# AnemometerTHT.net
KiCad netlist of a schematic drawn in EAGLE
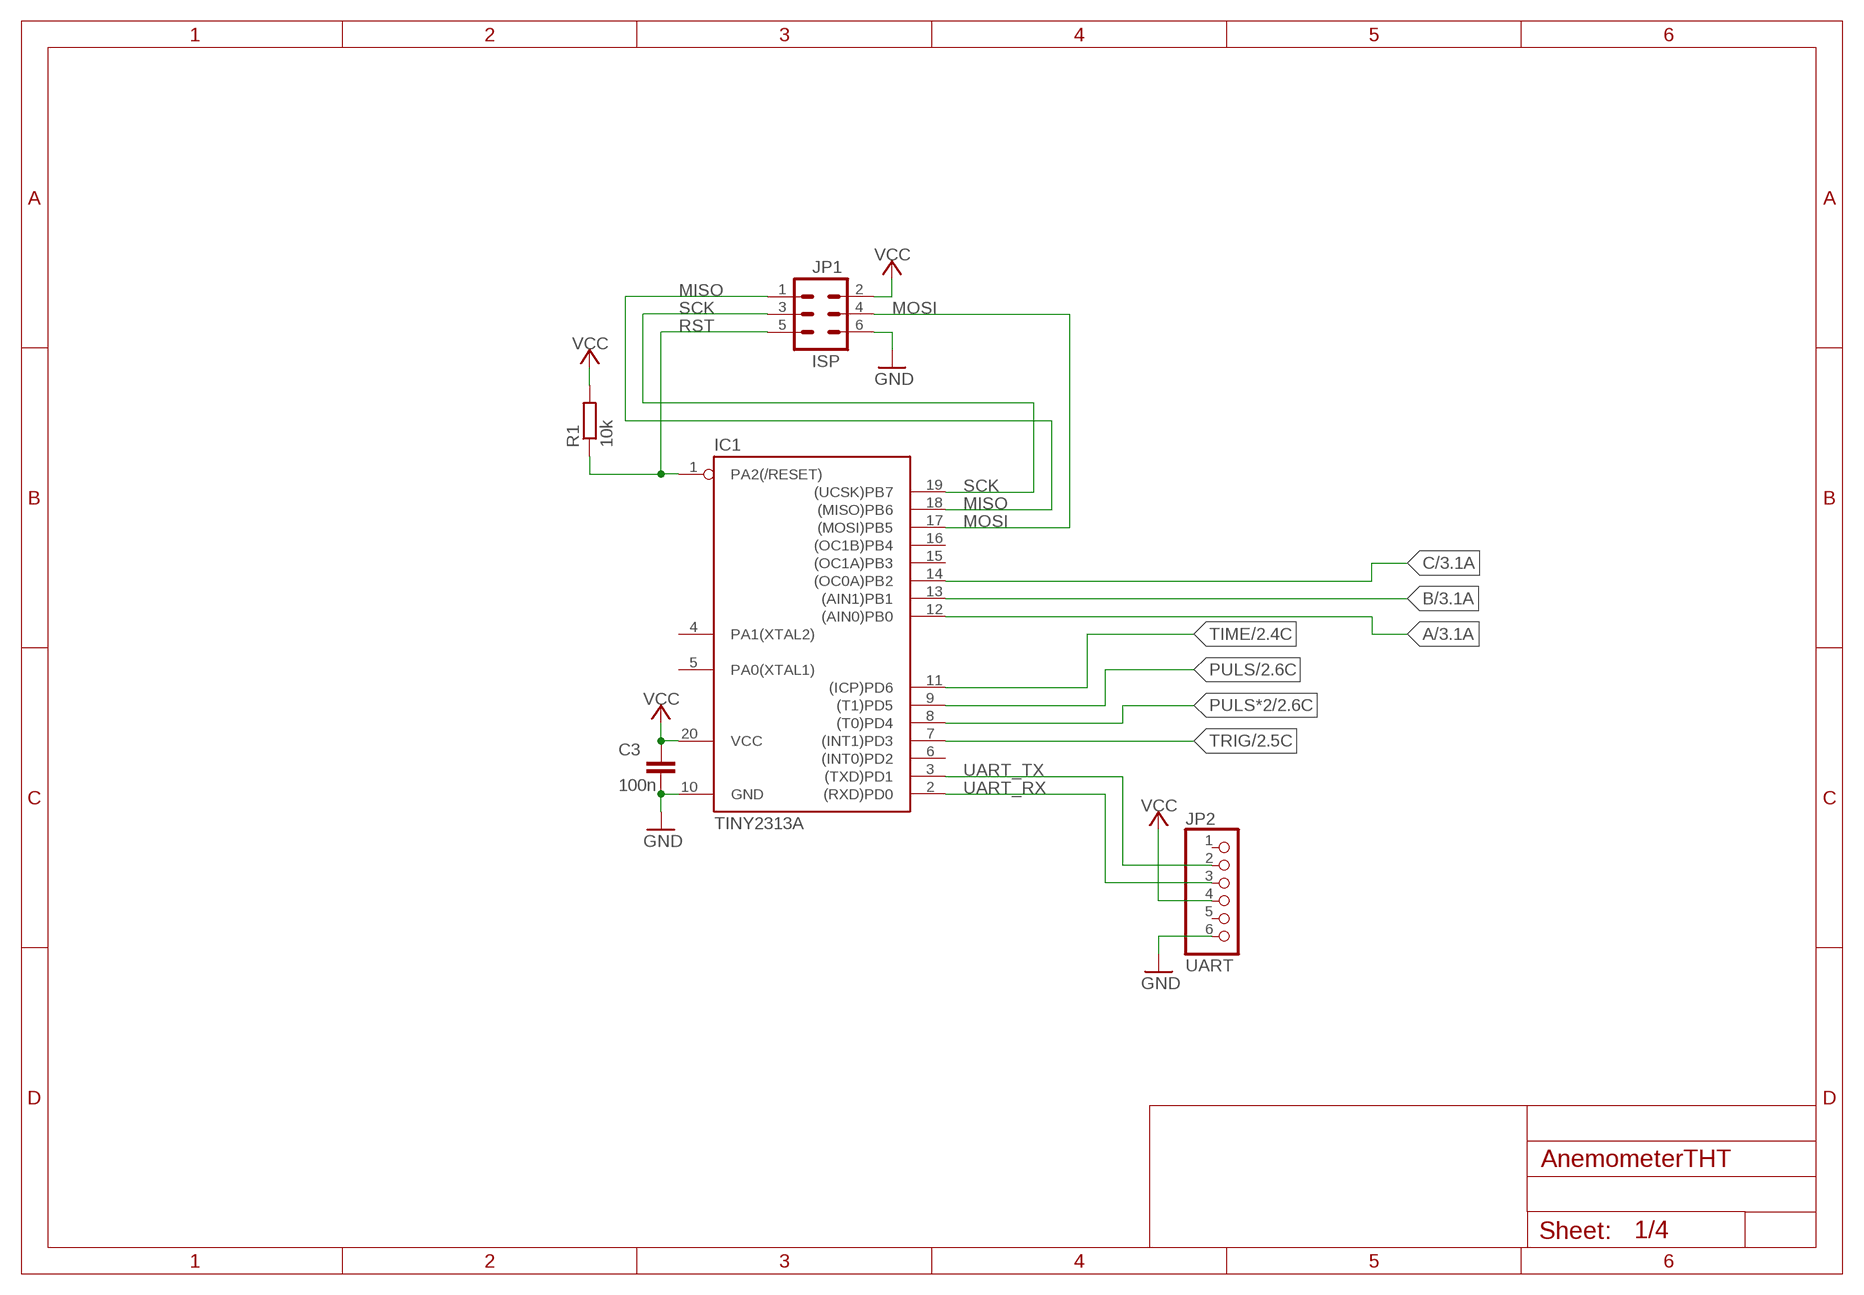
[diagram p0: schematic, sheet 1]
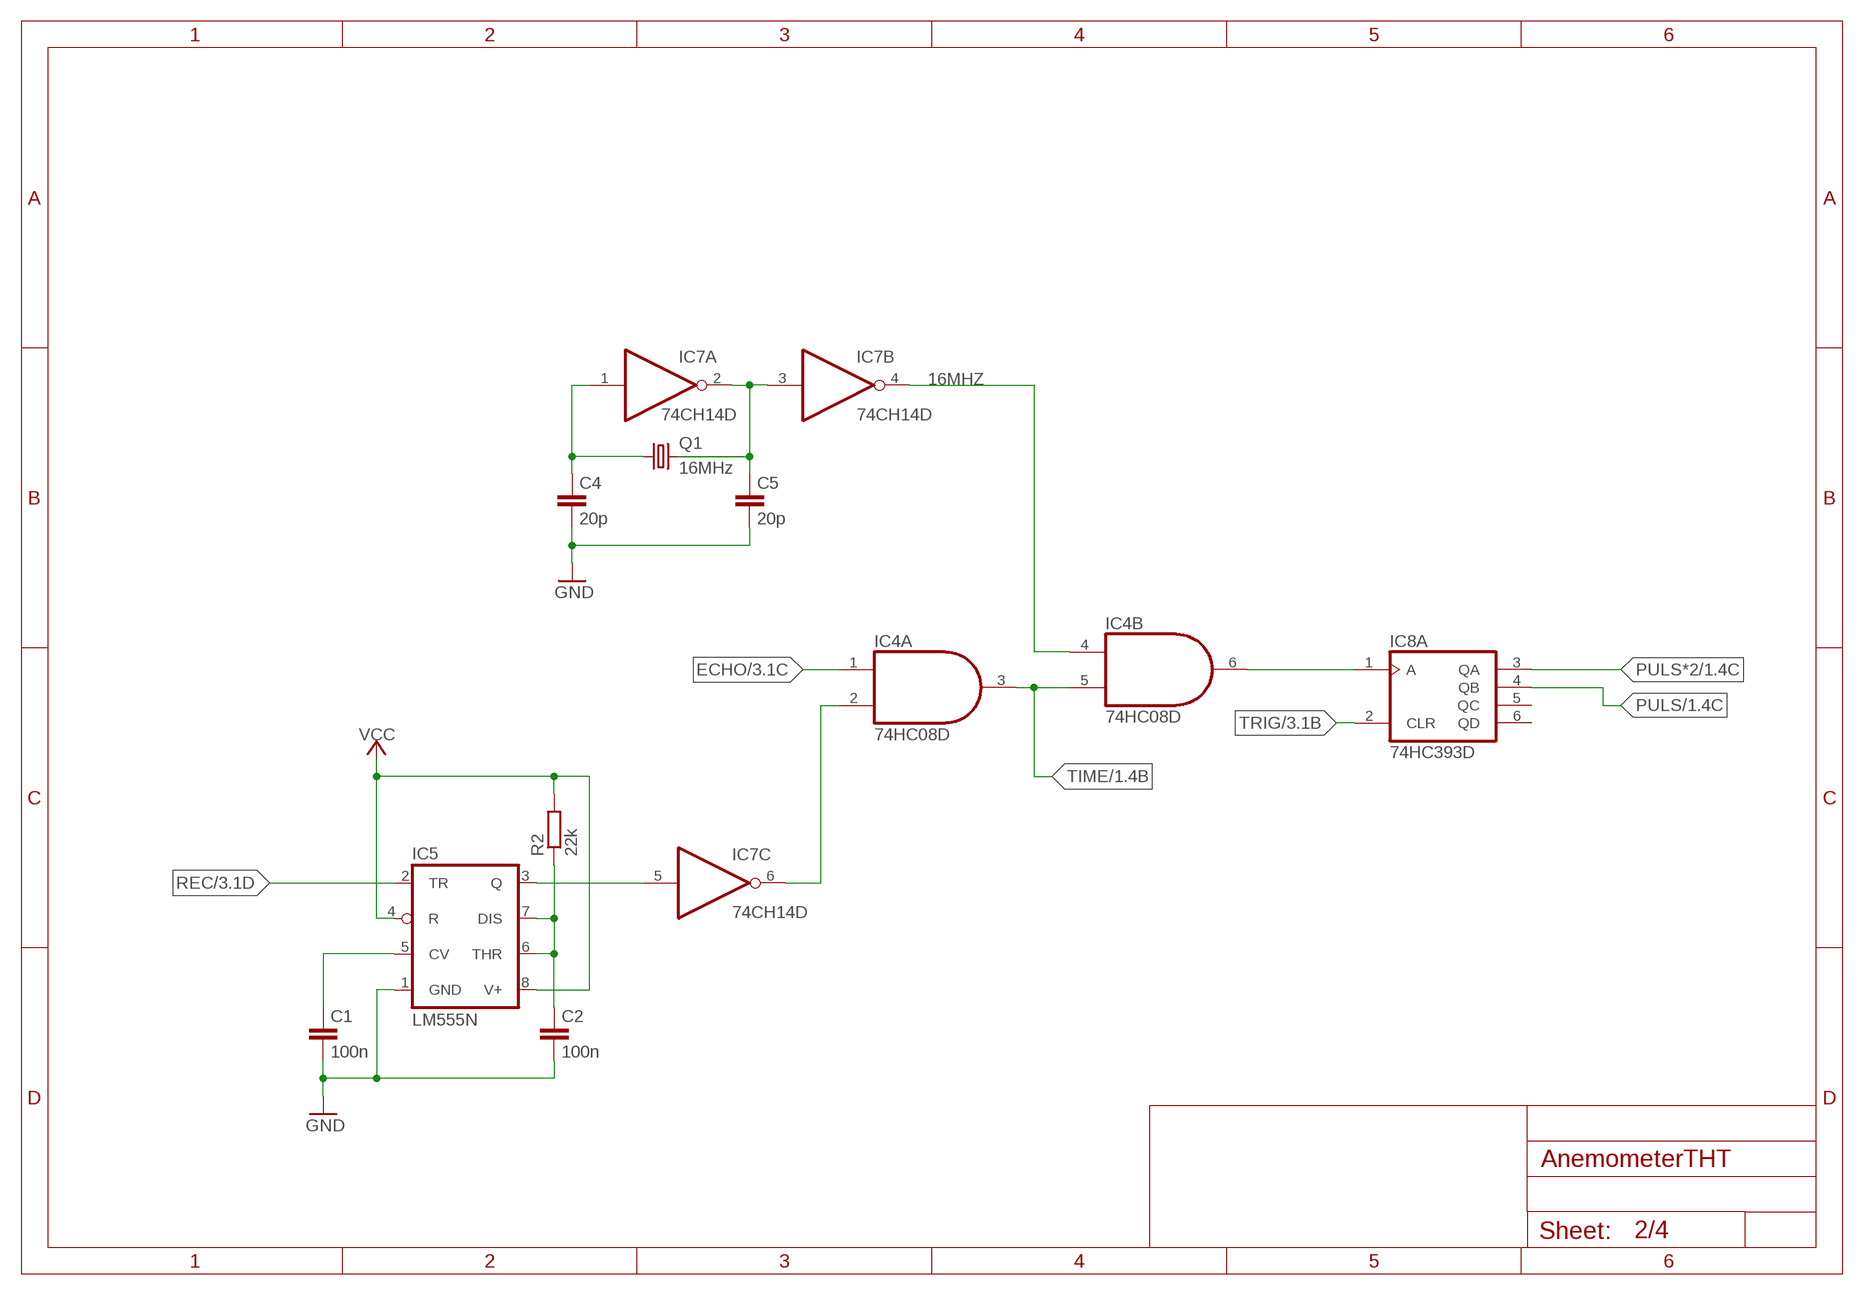
[diagram p1: schematic, sheet 2]
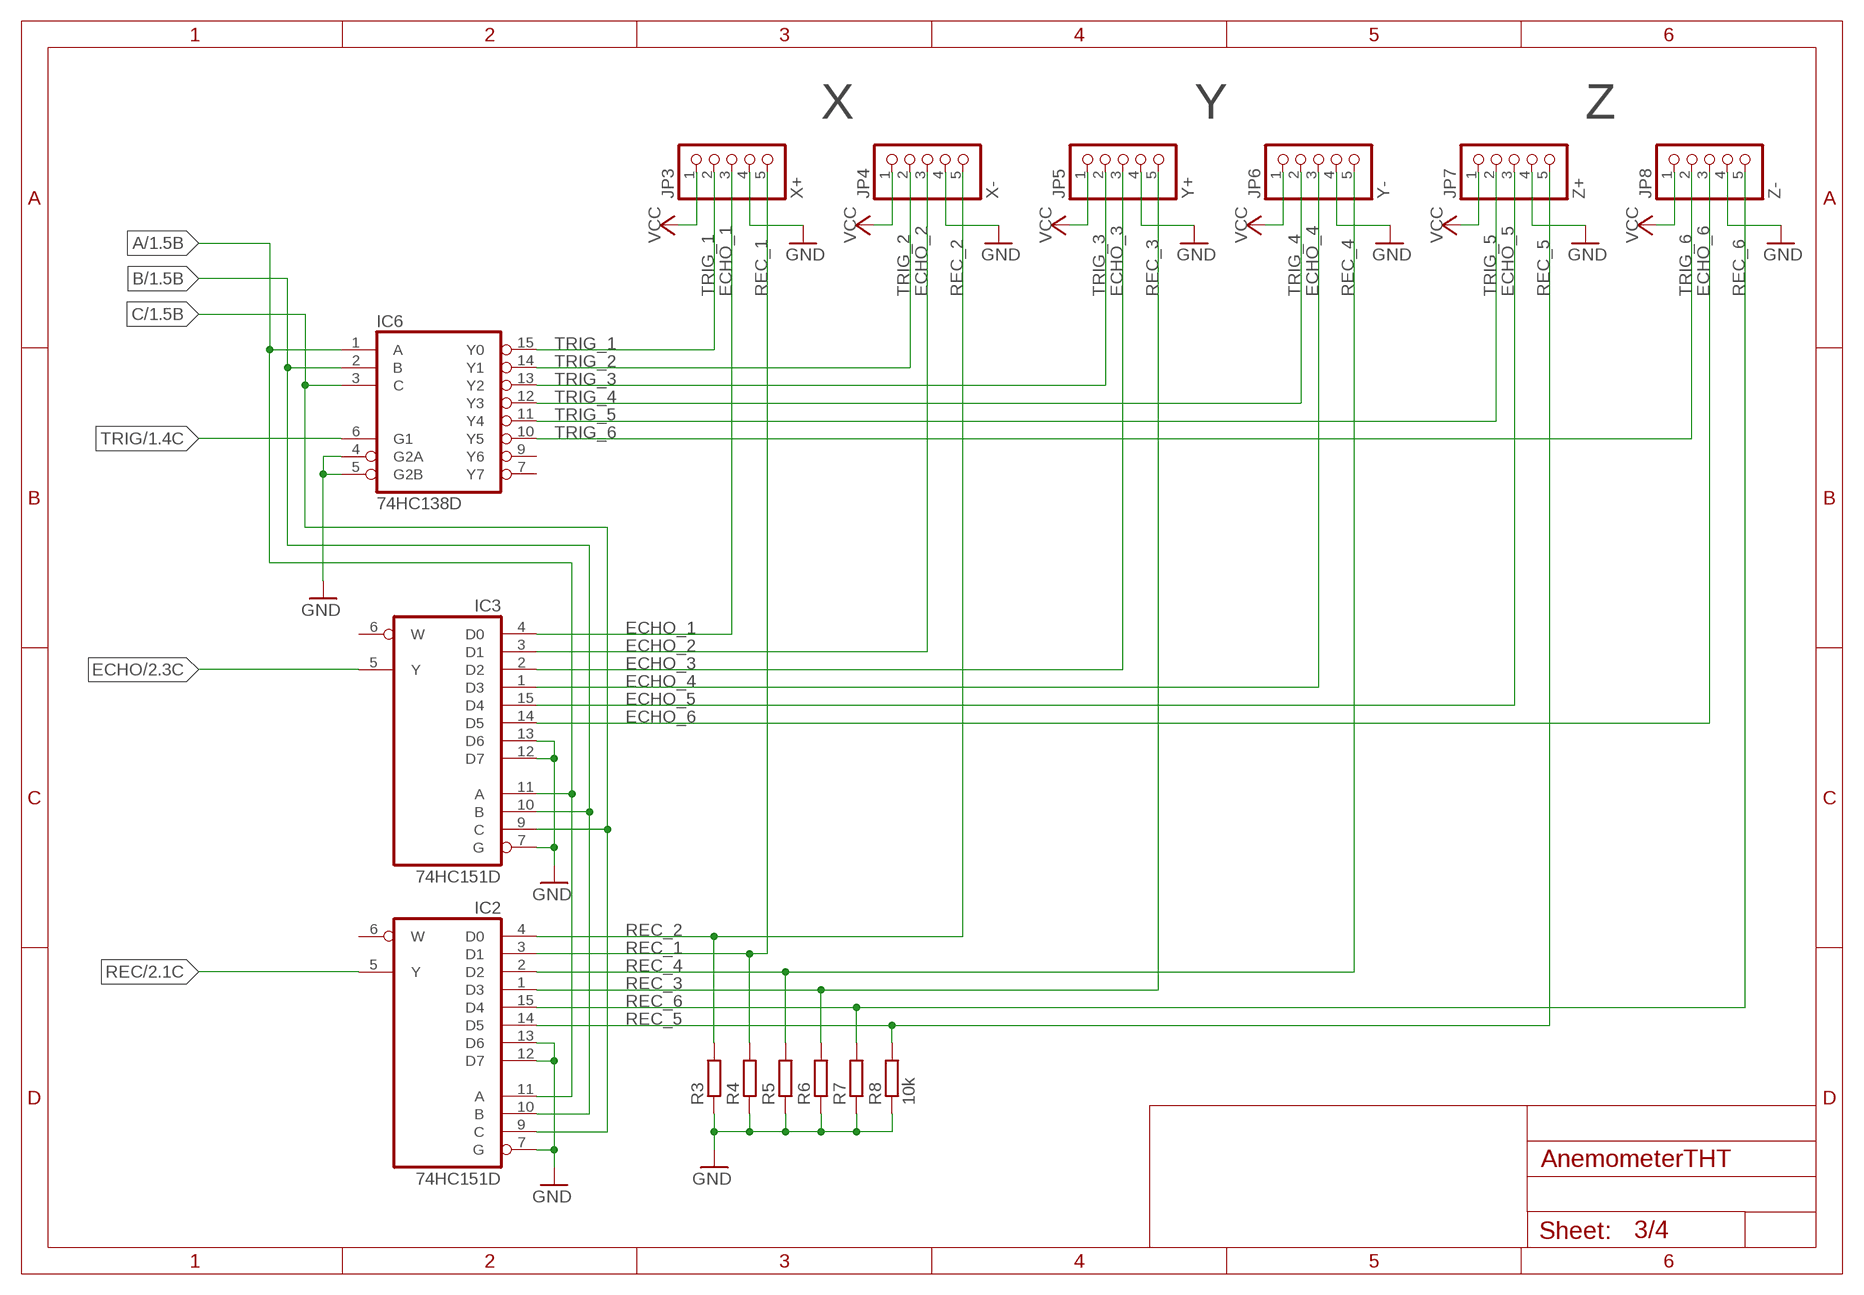
[diagram p2: schematic, sheet 3]
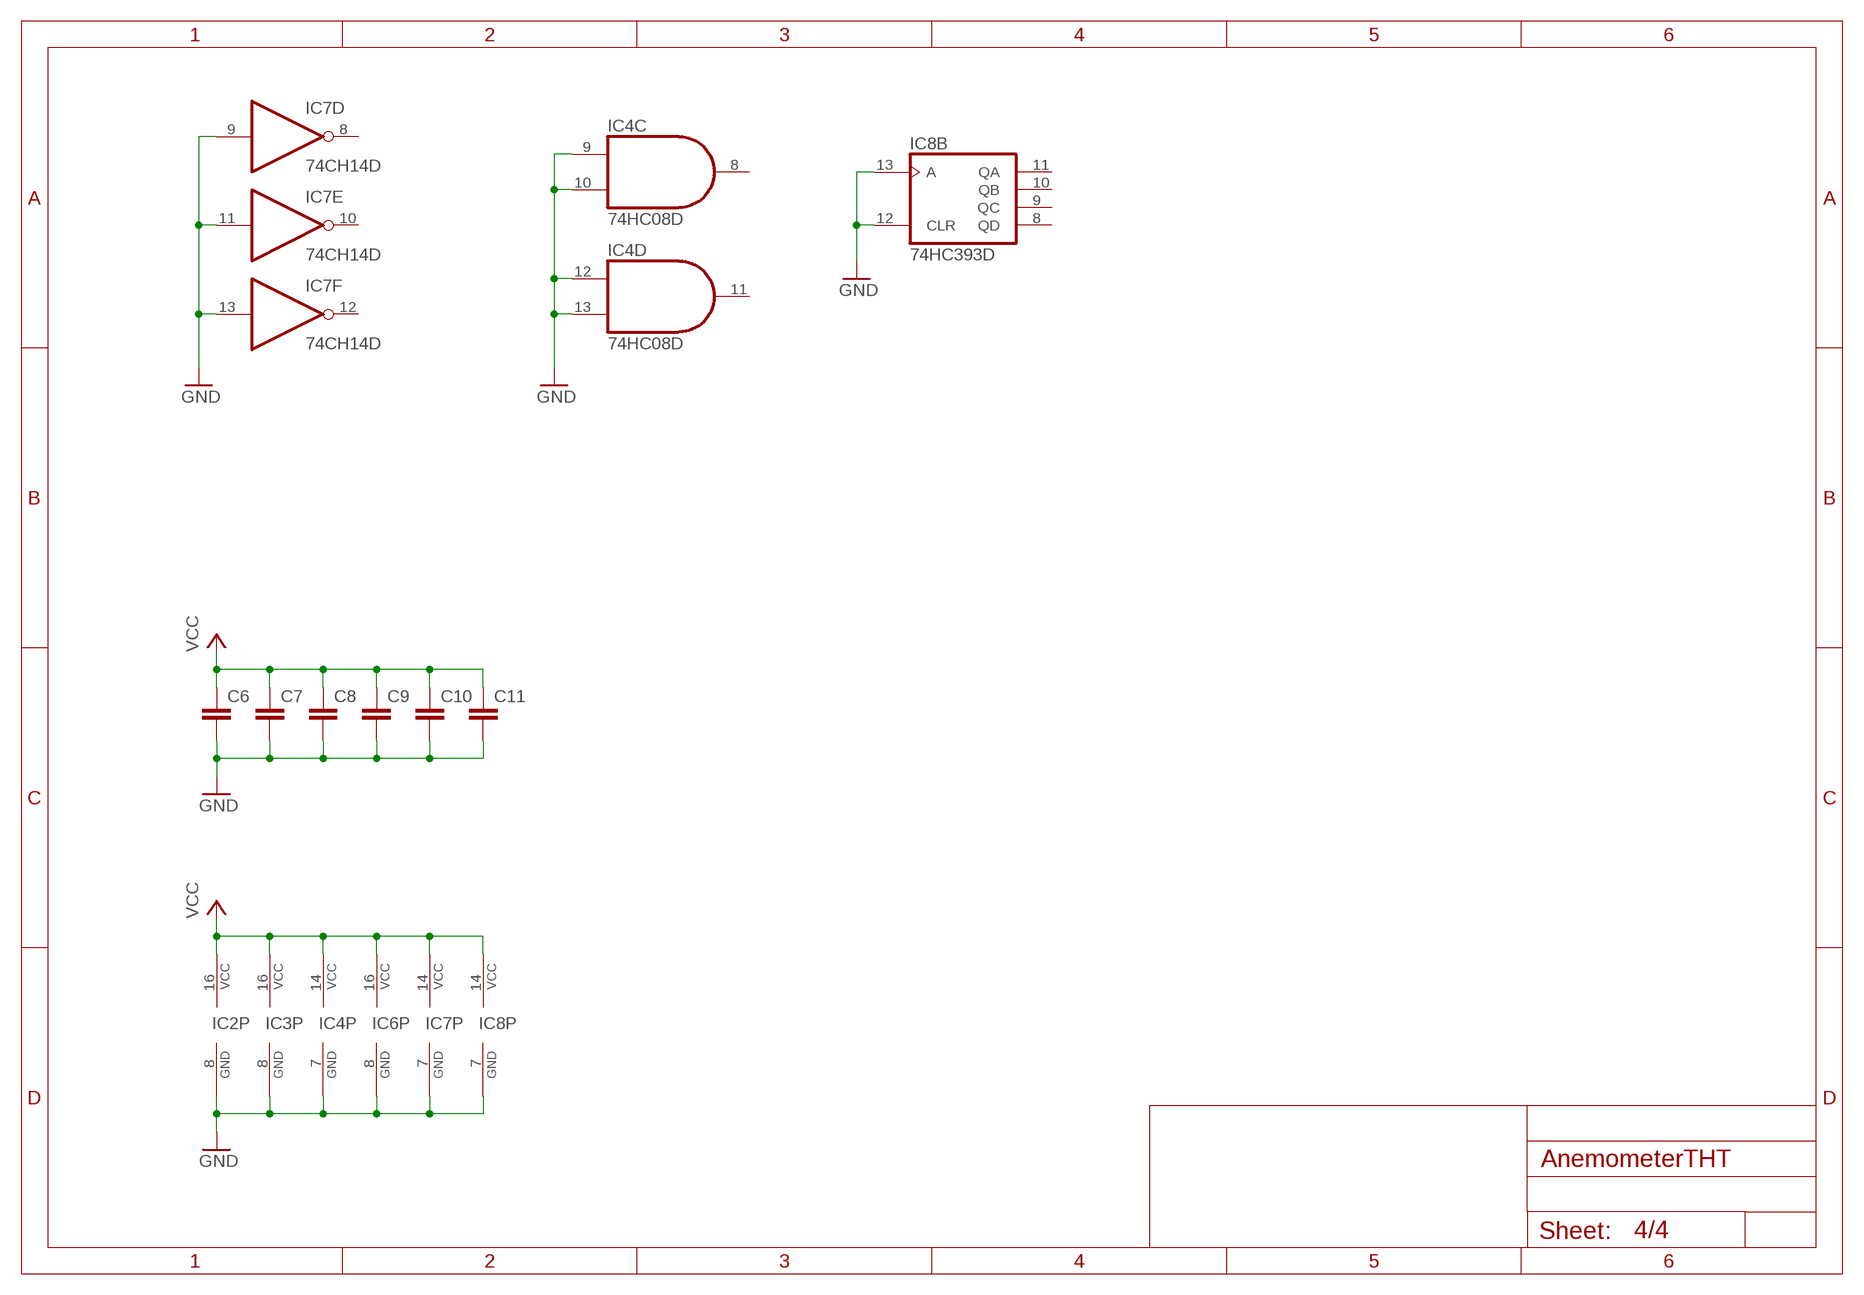
[diagram p3: schematic, sheet 4]

(export (version "E")
  (design (tool "Eeschema 10.0.6"))
  (components
    (comp (ref "IC2")
      (value "74HC151D")
      (footprint "eagle-import:DIL16")
      (libsource (lib "eagle-import") (part "74151NLS"))
    )
    (comp (ref "IC3")
      (value "74HC151D")
      (footprint "eagle-import:DIL16")
      (libsource (lib "eagle-import") (part "74151NLS"))
    )
    (comp (ref "IC6")
      (value "74HC138D")
      (footprint "eagle-import:DIL16")
      (libsource (lib "eagle-import") (part "74138NLS"))
    )
    (comp (ref "JP3")
      (value "X+")
      (footprint "eagle-import:1X05")
      (libsource (lib "eagle-import") (part "PINHD-1X5"))
    )
    (comp (ref "JP4")
      (value "X-")
      (footprint "eagle-import:1X05")
      (libsource (lib "eagle-import") (part "PINHD-1X5"))
    )
    (comp (ref "JP5")
      (value "Y+")
      (footprint "eagle-import:1X05")
      (libsource (lib "eagle-import") (part "PINHD-1X5"))
    )
    (comp (ref "JP6")
      (value "Y-")
      (footprint "eagle-import:1X05")
      (libsource (lib "eagle-import") (part "PINHD-1X5"))
    )
    (comp (ref "JP7")
      (value "Z+")
      (footprint "eagle-import:1X05")
      (libsource (lib "eagle-import") (part "PINHD-1X5"))
    )
    (comp (ref "JP8")
      (value "Z-")
      (footprint "eagle-import:1X05")
      (libsource (lib "eagle-import") (part "PINHD-1X5"))
    )
    (comp (ref "R3")
      (value "10k")
      (footprint "eagle-import:0204_7")
      (libsource (lib "eagle-import") (part "R-EU_0204/7"))
    )
    (comp (ref "R4")
      (value "10k")
      (footprint "eagle-import:0204_7")
      (libsource (lib "eagle-import") (part "R-EU_0204/7"))
    )
    (comp (ref "R5")
      (value "10k")
      (footprint "eagle-import:0204_7")
      (libsource (lib "eagle-import") (part "R-EU_0204/7"))
    )
    (comp (ref "R6")
      (value "10k")
      (footprint "eagle-import:0204_7")
      (libsource (lib "eagle-import") (part "R-EU_0204/7"))
    )
    (comp (ref "R7")
      (value "10k")
      (footprint "eagle-import:0204_7")
      (libsource (lib "eagle-import") (part "R-EU_0204/7"))
    )
    (comp (ref "R8")
      (value "10k")
      (footprint "eagle-import:0204_7")
      (libsource (lib "eagle-import") (part "R-EU_0204/7"))
    )
    (comp (ref "C6")
      (value "C-EU050-030X075")
      (footprint "eagle-import:C050-030X075")
      (libsource (lib "eagle-import") (part "C-EU050-030X075"))
    )
    (comp (ref "C7")
      (value "C-EU050-030X075")
      (footprint "eagle-import:C050-030X075")
      (libsource (lib "eagle-import") (part "C-EU050-030X075"))
    )
    (comp (ref "C8")
      (value "C-EU050-030X075")
      (footprint "eagle-import:C050-030X075")
      (libsource (lib "eagle-import") (part "C-EU050-030X075"))
    )
    (comp (ref "C9")
      (value "C-EU050-030X075")
      (footprint "eagle-import:C050-030X075")
      (libsource (lib "eagle-import") (part "C-EU050-030X075"))
    )
    (comp (ref "C10")
      (value "C-EU050-030X075")
      (footprint "eagle-import:C050-030X075")
      (libsource (lib "eagle-import") (part "C-EU050-030X075"))
    )
    (comp (ref "C11")
      (value "C-EU050-030X075")
      (footprint "eagle-import:C050-030X075")
      (libsource (lib "eagle-import") (part "C-EU050-030X075"))
    )
    (comp (ref "IC4")
      (value "74HC08D")
      (footprint "eagle-import:DIL14")
      (libsource (lib "eagle-import") (part "7408NALS"))
    )
    (comp (ref "IC7")
      (value "74CH14D")
      (footprint "eagle-import:DIL14")
      (libsource (lib "eagle-import") (part "7404NALS"))
    )
    (comp (ref "IC8")
      (value "74HC393D")
      (footprint "eagle-import:DIL14")
      (libsource (lib "eagle-import") (part "74393NLS"))
    )
    (comp (ref "C1")
      (value "100n")
      (footprint "eagle-import:C050-030X075")
      (libsource (lib "eagle-import") (part "C-EU050-030X075"))
    )
    (comp (ref "C2")
      (value "100n")
      (footprint "eagle-import:C050-030X075")
      (libsource (lib "eagle-import") (part "C-EU050-030X075"))
    )
    (comp (ref "C4")
      (value "20p")
      (footprint "eagle-import:C050-030X075")
      (libsource (lib "eagle-import") (part "C-EU050-030X075"))
    )
    (comp (ref "C5")
      (value "20p")
      (footprint "eagle-import:C050-030X075")
      (libsource (lib "eagle-import") (part "C-EU050-030X075"))
    )
    (comp (ref "IC5")
      (value "LM555N")
      (footprint "eagle-import:DIL08")
      (libsource (lib "eagle-import") (part "555NLM"))
    )
    (comp (ref "Q1")
      (value "16MHz")
      (footprint "eagle-import:HC49U70")
      (libsource (lib "eagle-import") (part "CRYSTALHC49U70"))
    )
    (comp (ref "R2")
      (value "22k")
      (footprint "eagle-import:0204_7")
      (libsource (lib "eagle-import") (part "R-EU_0204/7"))
    )
    (comp (ref "C3")
      (value "100n")
      (footprint "eagle-import:C050-030X075")
      (libsource (lib "eagle-import") (part "C-EU050-030X075"))
    )
    (comp (ref "IC1")
      (value "TINY2313A")
      (footprint "eagle-import:DIL20")
      (libsource (lib "eagle-import") (part "TINY2313-P"))
    )
    (comp (ref "JP1")
      (value "ISP")
      (footprint "eagle-import:ML6")
      (libsource (lib "eagle-import") (part "ML6"))
    )
    (comp (ref "JP2")
      (value "UART")
      (footprint "eagle-import:1X06")
      (libsource (lib "eagle-import") (part "PINHD-1X6"))
    )
    (comp (ref "R1")
      (value "10k")
      (footprint "eagle-import:0204_7")
      (libsource (lib "eagle-import") (part "R-EU_0204/7"))
    )
  )
  (nets
    (net (code "1") (name "16MHZ") (class "Default")
      (node (ref "IC4") (pin "4") (pinfunction "I0_4") (pintype "input"))
      (node (ref "IC7") (pin "4") (pinfunction "O_4") (pintype "output"))
    )
    (net (code "2") (name "A") (class "Default")
      (node (ref "IC1") (pin "12") (pinfunction "(AIN0)PB0_12") (pintype "bidirectional"))
      (node (ref "IC2") (pin "11") (pinfunction "A_11") (pintype "input"))
      (node (ref "IC3") (pin "11") (pinfunction "A_11") (pintype "input"))
      (node (ref "IC6") (pin "1") (pinfunction "A_1") (pintype "input"))
    )
    (net (code "3") (name "B") (class "Default")
      (node (ref "IC1") (pin "13") (pinfunction "(AIN1)PB1_13") (pintype "bidirectional"))
      (node (ref "IC2") (pin "10") (pinfunction "B_10") (pintype "input"))
      (node (ref "IC3") (pin "10") (pinfunction "B_10") (pintype "input"))
      (node (ref "IC6") (pin "2") (pinfunction "B_2") (pintype "input"))
    )
    (net (code "4") (name "C") (class "Default")
      (node (ref "IC1") (pin "14") (pinfunction "(OC0A)PB2_14") (pintype "bidirectional"))
      (node (ref "IC2") (pin "9") (pinfunction "C_9") (pintype "input"))
      (node (ref "IC3") (pin "9") (pinfunction "C_9") (pintype "input"))
      (node (ref "IC6") (pin "3") (pinfunction "C_3") (pintype "input"))
    )
    (net (code "5") (name "ECHO") (class "Default")
      (node (ref "IC3") (pin "5") (pinfunction "Y_5") (pintype "output"))
      (node (ref "IC4") (pin "1") (pinfunction "I0_1") (pintype "input"))
    )
    (net (code "6") (name "ECHO_1") (class "Default")
      (node (ref "IC3") (pin "4") (pinfunction "D0_4") (pintype "input"))
      (node (ref "JP3") (pin "3") (pinfunction "3_3") (pintype "passive"))
    )
    (net (code "7") (name "ECHO_2") (class "Default")
      (node (ref "IC3") (pin "3") (pinfunction "D1_3") (pintype "input"))
      (node (ref "JP4") (pin "3") (pinfunction "3_3") (pintype "passive"))
    )
    (net (code "8") (name "ECHO_3") (class "Default")
      (node (ref "IC3") (pin "2") (pinfunction "D2_2") (pintype "input"))
      (node (ref "JP5") (pin "3") (pinfunction "3_3") (pintype "passive"))
    )
    (net (code "9") (name "ECHO_4") (class "Default")
      (node (ref "IC3") (pin "1") (pinfunction "D3_1") (pintype "input"))
      (node (ref "JP6") (pin "3") (pinfunction "3_3") (pintype "passive"))
    )
    (net (code "10") (name "ECHO_5") (class "Default")
      (node (ref "IC3") (pin "15") (pinfunction "D4_15") (pintype "input"))
      (node (ref "JP7") (pin "3") (pinfunction "3_3") (pintype "passive"))
    )
    (net (code "11") (name "ECHO_6") (class "Default")
      (node (ref "IC3") (pin "14") (pinfunction "D5_14") (pintype "input"))
      (node (ref "JP8") (pin "3") (pinfunction "3_3") (pintype "passive"))
    )
    (net (code "12") (name "GND") (class "Default")
      (node (ref "C1") (pin "2") (pinfunction "2_2") (pintype "passive"))
      (node (ref "C10") (pin "2") (pinfunction "2_2") (pintype "passive"))
      (node (ref "C11") (pin "2") (pinfunction "2_2") (pintype "passive"))
      (node (ref "C2") (pin "2") (pinfunction "2_2") (pintype "passive"))
      (node (ref "C3") (pin "2") (pinfunction "2_2") (pintype "passive"))
      (node (ref "C4") (pin "2") (pinfunction "2_2") (pintype "passive"))
      (node (ref "C5") (pin "2") (pinfunction "2_2") (pintype "passive"))
      (node (ref "C6") (pin "2") (pinfunction "2_2") (pintype "passive"))
      (node (ref "C7") (pin "2") (pinfunction "2_2") (pintype "passive"))
      (node (ref "C8") (pin "2") (pinfunction "2_2") (pintype "passive"))
      (node (ref "C9") (pin "2") (pinfunction "2_2") (pintype "passive"))
      (node (ref "IC1") (pin "10") (pinfunction "GND_10") (pintype "power_in"))
      (node (ref "IC2") (pin "12") (pinfunction "D7_12") (pintype "input"))
      (node (ref "IC2") (pin "13") (pinfunction "D6_13") (pintype "input"))
      (node (ref "IC2") (pin "7") (pinfunction "G_7") (pintype "input"))
      (node (ref "IC2") (pin "8") (pinfunction "GND_8") (pintype "power_in"))
      (node (ref "IC3") (pin "12") (pinfunction "D7_12") (pintype "input"))
      (node (ref "IC3") (pin "13") (pinfunction "D6_13") (pintype "input"))
      (node (ref "IC3") (pin "7") (pinfunction "G_7") (pintype "input"))
      (node (ref "IC3") (pin "8") (pinfunction "GND_8") (pintype "power_in"))
      (node (ref "IC4") (pin "10") (pinfunction "I1_10") (pintype "input"))
      (node (ref "IC4") (pin "12") (pinfunction "I0_12") (pintype "input"))
      (node (ref "IC4") (pin "13") (pinfunction "I1_13") (pintype "input"))
      (node (ref "IC4") (pin "7") (pinfunction "GND_7") (pintype "power_in"))
      (node (ref "IC4") (pin "9") (pinfunction "I0_9") (pintype "input"))
      (node (ref "IC5") (pin "1") (pinfunction "GND_1") (pintype "power_in"))
      (node (ref "IC6") (pin "4") (pinfunction "G2A_4") (pintype "input"))
      (node (ref "IC6") (pin "5") (pinfunction "G2B_5") (pintype "input"))
      (node (ref "IC6") (pin "8") (pinfunction "GND_8") (pintype "power_in"))
      (node (ref "IC7") (pin "11") (pinfunction "I_11") (pintype "input"))
      (node (ref "IC7") (pin "13") (pinfunction "I_13") (pintype "input"))
      (node (ref "IC7") (pin "7") (pinfunction "GND_7") (pintype "power_in"))
      (node (ref "IC7") (pin "9") (pinfunction "I_9") (pintype "input"))
      (node (ref "IC8") (pin "12") (pinfunction "CLR_12") (pintype "input"))
      (node (ref "IC8") (pin "13") (pinfunction "A_13") (pintype "input"))
      (node (ref "IC8") (pin "7") (pinfunction "GND_7") (pintype "power_in"))
      (node (ref "JP1") (pin "6") (pinfunction "6_6") (pintype "passive"))
      (node (ref "JP2") (pin "6") (pinfunction "6_6") (pintype "passive"))
      (node (ref "JP3") (pin "4") (pinfunction "4_4") (pintype "passive"))
      (node (ref "JP4") (pin "4") (pinfunction "4_4") (pintype "passive"))
      (node (ref "JP5") (pin "4") (pinfunction "4_4") (pintype "passive"))
      (node (ref "JP6") (pin "4") (pinfunction "4_4") (pintype "passive"))
      (node (ref "JP7") (pin "4") (pinfunction "4_4") (pintype "passive"))
      (node (ref "JP8") (pin "4") (pinfunction "4_4") (pintype "passive"))
      (node (ref "R3") (pin "1") (pinfunction "1_1") (pintype "passive"))
      (node (ref "R4") (pin "1") (pinfunction "1_1") (pintype "passive"))
      (node (ref "R5") (pin "1") (pinfunction "1_1") (pintype "passive"))
      (node (ref "R6") (pin "1") (pinfunction "1_1") (pintype "passive"))
      (node (ref "R7") (pin "1") (pinfunction "1_1") (pintype "passive"))
      (node (ref "R8") (pin "1") (pinfunction "1_1") (pintype "passive"))
    )
    (net (code "13") (name "MISO") (class "Default")
      (node (ref "IC1") (pin "18") (pinfunction "(MISO)PB6_18") (pintype "bidirectional"))
      (node (ref "JP1") (pin "1") (pinfunction "1_1") (pintype "passive"))
    )
    (net (code "14") (name "MOSI") (class "Default")
      (node (ref "IC1") (pin "17") (pinfunction "(MOSI)PB5_17") (pintype "bidirectional"))
      (node (ref "JP1") (pin "4") (pinfunction "4_4") (pintype "passive"))
    )
    (net (code "15") (name "Net-(IC4A-I1)") (class "Default")
      (node (ref "IC4") (pin "2") (pinfunction "I1_2") (pintype "input"))
      (node (ref "IC7") (pin "6") (pinfunction "O_6") (pintype "output"))
    )
    (net (code "16") (name "Net-(IC4B-O)") (class "Default")
      (node (ref "IC4") (pin "6") (pinfunction "O_6") (pintype "output"))
      (node (ref "IC8") (pin "1") (pinfunction "A_1") (pintype "input"))
    )
    (net (code "17") (name "Net-(IC5-CV)") (class "Default")
      (node (ref "C1") (pin "1") (pinfunction "1_1") (pintype "passive"))
      (node (ref "IC5") (pin "5") (pinfunction "CV_5") (pintype "input"))
    )
    (net (code "18") (name "Net-(IC5-DIS)") (class "Default")
      (node (ref "C2") (pin "1") (pinfunction "1_1") (pintype "passive"))
      (node (ref "IC5") (pin "6") (pinfunction "THR_6") (pintype "input"))
      (node (ref "IC5") (pin "7") (pinfunction "DIS_7") (pintype "input"))
      (node (ref "R2") (pin "1") (pinfunction "1_1") (pintype "passive"))
    )
    (net (code "19") (name "Net-(IC5-Q)") (class "Default")
      (node (ref "IC5") (pin "3") (pinfunction "Q_3") (pintype "output"))
      (node (ref "IC7") (pin "5") (pinfunction "I_5") (pintype "input"))
    )
    (net (code "20") (name "Net-(IC7A-I)") (class "Default")
      (node (ref "C4") (pin "1") (pinfunction "1_1") (pintype "passive"))
      (node (ref "IC7") (pin "1") (pinfunction "I_1") (pintype "input"))
      (node (ref "Q1") (pin "1") (pinfunction "1_1") (pintype "passive"))
    )
    (net (code "21") (name "Net-(IC7A-O)") (class "Default")
      (node (ref "C5") (pin "1") (pinfunction "1_1") (pintype "passive"))
      (node (ref "IC7") (pin "2") (pinfunction "O_2") (pintype "output"))
      (node (ref "IC7") (pin "3") (pinfunction "I_3") (pintype "input"))
      (node (ref "Q1") (pin "2") (pinfunction "2_2") (pintype "passive"))
    )
    (net (code "22") (name "PULS") (class "Default")
      (node (ref "IC1") (pin "9") (pinfunction "(T1)PD5_9") (pintype "bidirectional"))
      (node (ref "IC8") (pin "4") (pinfunction "QB_4") (pintype "output"))
    )
    (net (code "23") (name "PULS*2") (class "Default")
      (node (ref "IC1") (pin "8") (pinfunction "(T0)PD4_8") (pintype "bidirectional"))
      (node (ref "IC8") (pin "3") (pinfunction "QA_3") (pintype "output"))
    )
    (net (code "24") (name "REC") (class "Default")
      (node (ref "IC2") (pin "5") (pinfunction "Y_5") (pintype "output"))
      (node (ref "IC5") (pin "2") (pinfunction "TR_2") (pintype "input"))
    )
    (net (code "25") (name "REC_1") (class "Default")
      (node (ref "IC2") (pin "3") (pinfunction "D1_3") (pintype "input"))
      (node (ref "JP3") (pin "5") (pinfunction "5_5") (pintype "passive"))
      (node (ref "R4") (pin "2") (pinfunction "2_2") (pintype "passive"))
    )
    (net (code "26") (name "REC_2") (class "Default")
      (node (ref "IC2") (pin "4") (pinfunction "D0_4") (pintype "input"))
      (node (ref "JP4") (pin "5") (pinfunction "5_5") (pintype "passive"))
      (node (ref "R3") (pin "2") (pinfunction "2_2") (pintype "passive"))
    )
    (net (code "27") (name "REC_3") (class "Default")
      (node (ref "IC2") (pin "1") (pinfunction "D3_1") (pintype "input"))
      (node (ref "JP5") (pin "5") (pinfunction "5_5") (pintype "passive"))
      (node (ref "R6") (pin "2") (pinfunction "2_2") (pintype "passive"))
    )
    (net (code "28") (name "REC_4") (class "Default")
      (node (ref "IC2") (pin "2") (pinfunction "D2_2") (pintype "input"))
      (node (ref "JP6") (pin "5") (pinfunction "5_5") (pintype "passive"))
      (node (ref "R5") (pin "2") (pinfunction "2_2") (pintype "passive"))
    )
    (net (code "29") (name "REC_5") (class "Default")
      (node (ref "IC2") (pin "14") (pinfunction "D5_14") (pintype "input"))
      (node (ref "JP7") (pin "5") (pinfunction "5_5") (pintype "passive"))
      (node (ref "R8") (pin "2") (pinfunction "2_2") (pintype "passive"))
    )
    (net (code "30") (name "REC_6") (class "Default")
      (node (ref "IC2") (pin "15") (pinfunction "D4_15") (pintype "input"))
      (node (ref "JP8") (pin "5") (pinfunction "5_5") (pintype "passive"))
      (node (ref "R7") (pin "2") (pinfunction "2_2") (pintype "passive"))
    )
    (net (code "31") (name "RST") (class "Default")
      (node (ref "IC1") (pin "1") (pinfunction "PA2(/RESET)_1") (pintype "input"))
      (node (ref "JP1") (pin "5") (pinfunction "5_5") (pintype "passive"))
      (node (ref "R1") (pin "1") (pinfunction "1_1") (pintype "passive"))
    )
    (net (code "32") (name "SCK") (class "Default")
      (node (ref "IC1") (pin "19") (pinfunction "(UCSK)PB7_19") (pintype "bidirectional"))
      (node (ref "JP1") (pin "3") (pinfunction "3_3") (pintype "passive"))
    )
    (net (code "33") (name "TIME") (class "Default")
      (node (ref "IC1") (pin "11") (pinfunction "(ICP)PD6_11") (pintype "bidirectional"))
      (node (ref "IC4") (pin "3") (pinfunction "O_3") (pintype "output"))
      (node (ref "IC4") (pin "5") (pinfunction "I1_5") (pintype "input"))
    )
    (net (code "34") (name "TRIG") (class "Default")
      (node (ref "IC1") (pin "7") (pinfunction "(INT1)PD3_7") (pintype "bidirectional"))
      (node (ref "IC6") (pin "6") (pinfunction "G1_6") (pintype "input"))
      (node (ref "IC8") (pin "2") (pinfunction "CLR_2") (pintype "input"))
    )
    (net (code "35") (name "TRIG_1") (class "Default")
      (node (ref "IC6") (pin "15") (pinfunction "Y0_15") (pintype "output"))
      (node (ref "JP3") (pin "2") (pinfunction "2_2") (pintype "passive"))
    )
    (net (code "36") (name "TRIG_2") (class "Default")
      (node (ref "IC6") (pin "14") (pinfunction "Y1_14") (pintype "output"))
      (node (ref "JP4") (pin "2") (pinfunction "2_2") (pintype "passive"))
    )
    (net (code "37") (name "TRIG_3") (class "Default")
      (node (ref "IC6") (pin "13") (pinfunction "Y2_13") (pintype "output"))
      (node (ref "JP5") (pin "2") (pinfunction "2_2") (pintype "passive"))
    )
    (net (code "38") (name "TRIG_4") (class "Default")
      (node (ref "IC6") (pin "12") (pinfunction "Y3_12") (pintype "output"))
      (node (ref "JP6") (pin "2") (pinfunction "2_2") (pintype "passive"))
    )
    (net (code "39") (name "TRIG_5") (class "Default")
      (node (ref "IC6") (pin "11") (pinfunction "Y4_11") (pintype "output"))
      (node (ref "JP7") (pin "2") (pinfunction "2_2") (pintype "passive"))
    )
    (net (code "40") (name "TRIG_6") (class "Default")
      (node (ref "IC6") (pin "10") (pinfunction "Y5_10") (pintype "output"))
      (node (ref "JP8") (pin "2") (pinfunction "2_2") (pintype "passive"))
    )
    (net (code "41") (name "UART_RX") (class "Default")
      (node (ref "IC1") (pin "2") (pinfunction "(RXD)PD0_2") (pintype "bidirectional"))
      (node (ref "JP2") (pin "3") (pinfunction "3_3") (pintype "passive"))
    )
    (net (code "42") (name "UART_TX") (class "Default")
      (node (ref "IC1") (pin "3") (pinfunction "(TXD)PD1_3") (pintype "bidirectional"))
      (node (ref "JP2") (pin "2") (pinfunction "2_2") (pintype "passive"))
    )
    (net (code "43") (name "VCC") (class "Default")
      (node (ref "C10") (pin "1") (pinfunction "1_1") (pintype "passive"))
      (node (ref "C11") (pin "1") (pinfunction "1_1") (pintype "passive"))
      (node (ref "C3") (pin "1") (pinfunction "1_1") (pintype "passive"))
      (node (ref "C6") (pin "1") (pinfunction "1_1") (pintype "passive"))
      (node (ref "C7") (pin "1") (pinfunction "1_1") (pintype "passive"))
      (node (ref "C8") (pin "1") (pinfunction "1_1") (pintype "passive"))
      (node (ref "C9") (pin "1") (pinfunction "1_1") (pintype "passive"))
      (node (ref "IC1") (pin "20") (pinfunction "VCC_20") (pintype "power_in"))
      (node (ref "IC2") (pin "16") (pinfunction "VCC_16") (pintype "power_in"))
      (node (ref "IC3") (pin "16") (pinfunction "VCC_16") (pintype "power_in"))
      (node (ref "IC4") (pin "14") (pinfunction "VCC_14") (pintype "power_in"))
      (node (ref "IC5") (pin "4") (pinfunction "R_4") (pintype "input"))
      (node (ref "IC5") (pin "8") (pinfunction "V+_8") (pintype "power_in"))
      (node (ref "IC6") (pin "16") (pinfunction "VCC_16") (pintype "power_in"))
      (node (ref "IC7") (pin "14") (pinfunction "VCC_14") (pintype "power_in"))
      (node (ref "IC8") (pin "14") (pinfunction "VCC_14") (pintype "power_in"))
      (node (ref "JP1") (pin "2") (pinfunction "2_2") (pintype "passive"))
      (node (ref "JP2") (pin "4") (pinfunction "4_4") (pintype "passive"))
      (node (ref "JP3") (pin "1") (pinfunction "1_1") (pintype "passive"))
      (node (ref "JP4") (pin "1") (pinfunction "1_1") (pintype "passive"))
      (node (ref "JP5") (pin "1") (pinfunction "1_1") (pintype "passive"))
      (node (ref "JP6") (pin "1") (pinfunction "1_1") (pintype "passive"))
      (node (ref "JP7") (pin "1") (pinfunction "1_1") (pintype "passive"))
      (node (ref "JP8") (pin "1") (pinfunction "1_1") (pintype "passive"))
      (node (ref "R1") (pin "2") (pinfunction "2_2") (pintype "passive"))
      (node (ref "R2") (pin "2") (pinfunction "2_2") (pintype "passive"))
    )
    (net (code "44") (name "unconnected-(IC1-(INT0)PD2-Pad6)") (class "Default")
      (node (ref "IC1") (pin "6") (pinfunction "(INT0)PD2_6") (pintype "bidirectional"))
    )
    (net (code "45") (name "unconnected-(IC1-(OC1A)PB3-Pad15)") (class "Default")
      (node (ref "IC1") (pin "15") (pinfunction "(OC1A)PB3_15") (pintype "bidirectional"))
    )
    (net (code "46") (name "unconnected-(IC1-(OC1B)PB4-Pad16)") (class "Default")
      (node (ref "IC1") (pin "16") (pinfunction "(OC1B)PB4_16") (pintype "bidirectional"))
    )
    (net (code "47") (name "unconnected-(IC1-PA0(XTAL1)-Pad5)") (class "Default")
      (node (ref "IC1") (pin "5") (pinfunction "PA0(XTAL1)_5") (pintype "bidirectional"))
    )
    (net (code "48") (name "unconnected-(IC1-PA1(XTAL2)-Pad4)") (class "Default")
      (node (ref "IC1") (pin "4") (pinfunction "PA1(XTAL2)_4") (pintype "bidirectional"))
    )
    (net (code "49") (name "unconnected-(IC2A-W-Pad6)") (class "Default")
      (node (ref "IC2") (pin "6") (pinfunction "W_6") (pintype "output"))
    )
    (net (code "50") (name "unconnected-(IC3A-W-Pad6)") (class "Default")
      (node (ref "IC3") (pin "6") (pinfunction "W_6") (pintype "output"))
    )
    (net (code "51") (name "unconnected-(IC4C-O-Pad8)") (class "Default")
      (node (ref "IC4") (pin "8") (pinfunction "O_8") (pintype "output"))
    )
    (net (code "52") (name "unconnected-(IC4D-O-Pad11)") (class "Default")
      (node (ref "IC4") (pin "11") (pinfunction "O_11") (pintype "output"))
    )
    (net (code "53") (name "unconnected-(IC6A-Y6-Pad9)") (class "Default")
      (node (ref "IC6") (pin "9") (pinfunction "Y6_9") (pintype "output"))
    )
    (net (code "54") (name "unconnected-(IC6A-Y7-Pad7)") (class "Default")
      (node (ref "IC6") (pin "7") (pinfunction "Y7_7") (pintype "output"))
    )
    (net (code "55") (name "unconnected-(IC7D-O-Pad8)") (class "Default")
      (node (ref "IC7") (pin "8") (pinfunction "O_8") (pintype "output"))
    )
    (net (code "56") (name "unconnected-(IC7E-O-Pad10)") (class "Default")
      (node (ref "IC7") (pin "10") (pinfunction "O_10") (pintype "output"))
    )
    (net (code "57") (name "unconnected-(IC7F-O-Pad12)") (class "Default")
      (node (ref "IC7") (pin "12") (pinfunction "O_12") (pintype "output"))
    )
    (net (code "58") (name "unconnected-(IC8A-QC-Pad5)") (class "Default")
      (node (ref "IC8") (pin "5") (pinfunction "QC_5") (pintype "output"))
    )
    (net (code "59") (name "unconnected-(IC8A-QD-Pad6)") (class "Default")
      (node (ref "IC8") (pin "6") (pinfunction "QD_6") (pintype "output"))
    )
    (net (code "60") (name "unconnected-(IC8B-QA-Pad11)") (class "Default")
      (node (ref "IC8") (pin "11") (pinfunction "QA_11") (pintype "output"))
    )
    (net (code "61") (name "unconnected-(IC8B-QB-Pad10)") (class "Default")
      (node (ref "IC8") (pin "10") (pinfunction "QB_10") (pintype "output"))
    )
    (net (code "62") (name "unconnected-(IC8B-QC-Pad9)") (class "Default")
      (node (ref "IC8") (pin "9") (pinfunction "QC_9") (pintype "output"))
    )
    (net (code "63") (name "unconnected-(IC8B-QD-Pad8)") (class "Default")
      (node (ref "IC8") (pin "8") (pinfunction "QD_8") (pintype "output"))
    )
    (net (code "64") (name "unconnected-(JP2-Pad1)") (class "Default")
      (node (ref "JP2") (pin "1") (pinfunction "1_1") (pintype "passive"))
    )
    (net (code "65") (name "unconnected-(JP2-Pad5)") (class "Default")
      (node (ref "JP2") (pin "5") (pinfunction "5_5") (pintype "passive"))
    )
  )
)
